# Interlock.net
KiCad netlist of a schematic drawn in EAGLE
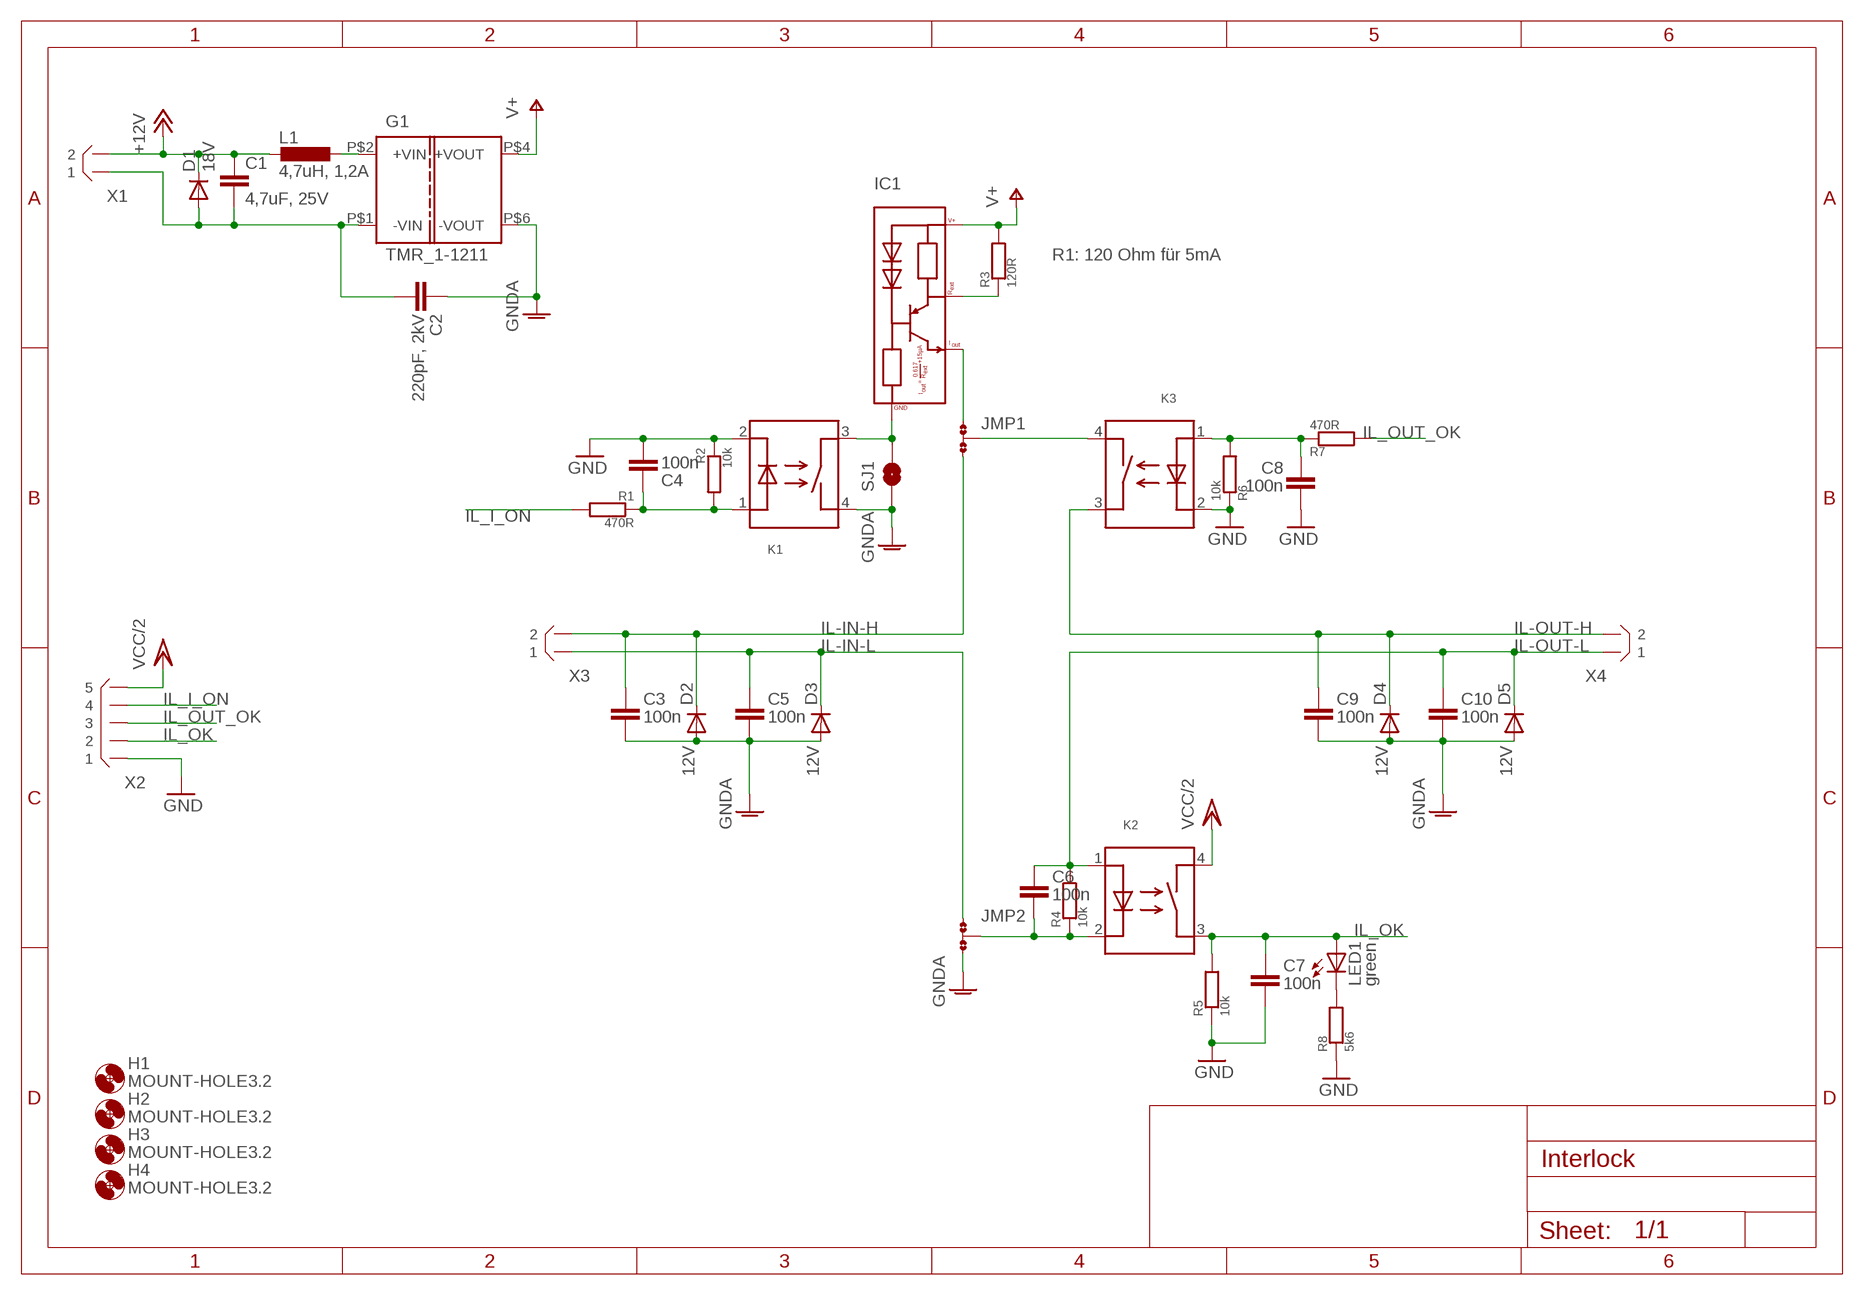
[diagram p0: schematic, sheet 1]

(export (version "E")
  (design (tool "Eeschema 10.0.6"))
  (components
    (comp (ref "C1")
      (value "4,7uF, 25V")
      (footprint "eagle-import:C0805")
      (libsource (lib "eagle-import") (part "C-EUC0805"))
    )
    (comp (ref "C2")
      (value "220pF, 2kV")
      (footprint "eagle-import:C1210_HV")
      (libsource (lib "eagle-import") (part "CC1210_HV"))
    )
    (comp (ref "C3")
      (value "100n")
      (footprint "eagle-import:C0805")
      (libsource (lib "eagle-import") (part "CSTD"))
    )
    (comp (ref "C4")
      (value "100n")
      (footprint "eagle-import:C0805")
      (libsource (lib "eagle-import") (part "CSTD"))
    )
    (comp (ref "C5")
      (value "100n")
      (footprint "eagle-import:C0805")
      (libsource (lib "eagle-import") (part "CSTD"))
    )
    (comp (ref "C6")
      (value "100n")
      (footprint "eagle-import:C0805")
      (libsource (lib "eagle-import") (part "CSTD"))
    )
    (comp (ref "C7")
      (value "100n")
      (footprint "eagle-import:C0805")
      (libsource (lib "eagle-import") (part "CSTD"))
    )
    (comp (ref "C8")
      (value "100n")
      (footprint "eagle-import:C0805")
      (libsource (lib "eagle-import") (part "CSTD"))
    )
    (comp (ref "C9")
      (value "100n")
      (footprint "eagle-import:C0805")
      (libsource (lib "eagle-import") (part "CSTD"))
    )
    (comp (ref "C10")
      (value "100n")
      (footprint "eagle-import:C0805")
      (libsource (lib "eagle-import") (part "CSTD"))
    )
    (comp (ref "D1")
      (value "18V")
      (footprint "eagle-import:DO214AA")
      (libsource (lib "eagle-import") (part "DIODE-DO214AA"))
    )
    (comp (ref "D2")
      (value "12V")
      (footprint "eagle-import:DO214AA")
      (libsource (lib "eagle-import") (part "DIODE-DO214AA"))
    )
    (comp (ref "D3")
      (value "12V")
      (footprint "eagle-import:DO214AA")
      (libsource (lib "eagle-import") (part "DIODE-DO214AA"))
    )
    (comp (ref "D4")
      (value "12V")
      (footprint "eagle-import:DO214AA")
      (libsource (lib "eagle-import") (part "DIODE-DO214AA"))
    )
    (comp (ref "D5")
      (value "12V")
      (footprint "eagle-import:DO214AA")
      (libsource (lib "eagle-import") (part "DIODE-DO214AA"))
    )
    (comp (ref "G1")
      (value "TMR_1-1211")
      (footprint "eagle-import:TMR_1-__1_")
      (libsource (lib "eagle-import") (part "TMR_1-??1?"))
    )
    (comp (ref "H1")
      (value "MOUNT-HOLE3.2")
      (footprint "eagle-import:3,2")
      (libsource (lib "eagle-import") (part "MOUNT-HOLE3.2"))
    )
    (comp (ref "H2")
      (value "MOUNT-HOLE3.2")
      (footprint "eagle-import:3,2")
      (libsource (lib "eagle-import") (part "MOUNT-HOLE3.2"))
    )
    (comp (ref "H3")
      (value "MOUNT-HOLE3.2")
      (footprint "eagle-import:3,2")
      (libsource (lib "eagle-import") (part "MOUNT-HOLE3.2"))
    )
    (comp (ref "H4")
      (value "MOUNT-HOLE3.2")
      (footprint "eagle-import:3,2")
      (libsource (lib "eagle-import") (part "MOUNT-HOLE3.2"))
    )
    (comp (ref "IC1")
      (value "PSSI2021SAY")
      (footprint "eagle-import:SOT353")
      (libsource (lib "eagle-import") (part "PSSI2021SAY"))
    )
    (comp (ref "JMP1")
      (value "0R-JUMPA")
      (footprint "eagle-import:A0R-JMP")
      (libsource (lib "eagle-import") (part "0R-JUMPA"))
    )
    (comp (ref "JMP2")
      (value "0R-JUMPA")
      (footprint "eagle-import:A0R-JMP")
      (libsource (lib "eagle-import") (part "0R-JUMPA"))
    )
    (comp (ref "K1")
      (value "ASSR-1218")
      (footprint "eagle-import:SO-4")
      (libsource (lib "eagle-import") (part "ASSR-1218"))
    )
    (comp (ref "K2")
      (value "ASSR-1218")
      (footprint "eagle-import:SO-4")
      (libsource (lib "eagle-import") (part "ASSR-1218"))
    )
    (comp (ref "K3")
      (value "ASSR-1218")
      (footprint "eagle-import:SO-4")
      (libsource (lib "eagle-import") (part "ASSR-1218"))
    )
    (comp (ref "L1")
      (value "4,7uH, 1,2A")
      (footprint "eagle-import:L3225M")
      (libsource (lib "eagle-import") (part "L-EUL3225M"))
    )
    (comp (ref "LED1")
      (value "green")
      (footprint "eagle-import:CHIPLED_0805")
      (libsource (lib "eagle-import") (part "LEDCHIPLED_0805"))
    )
    (comp (ref "R1")
      (value "470R")
      (footprint "eagle-import:R0805")
      (libsource (lib "eagle-import") (part "R"))
    )
    (comp (ref "R2")
      (value "10k")
      (footprint "eagle-import:R0805")
      (libsource (lib "eagle-import") (part "R"))
    )
    (comp (ref "R3")
      (value "120R")
      (footprint "eagle-import:R0805")
      (libsource (lib "eagle-import") (part "R"))
    )
    (comp (ref "R4")
      (value "10k")
      (footprint "eagle-import:R0805")
      (libsource (lib "eagle-import") (part "R"))
    )
    (comp (ref "R5")
      (value "10k")
      (footprint "eagle-import:R0805")
      (libsource (lib "eagle-import") (part "R"))
    )
    (comp (ref "R6")
      (value "10k")
      (footprint "eagle-import:R0805")
      (libsource (lib "eagle-import") (part "R"))
    )
    (comp (ref "R7")
      (value "470R")
      (footprint "eagle-import:R0805")
      (libsource (lib "eagle-import") (part "R"))
    )
    (comp (ref "R8")
      (value "5k6")
      (footprint "eagle-import:R0805")
      (libsource (lib "eagle-import") (part "R"))
    )
    (comp (ref "SJ1")
      (value "SOLDERJUMPERNO")
      (footprint "eagle-import:SJ_2S-NO")
      (libsource (lib "eagle-import") (part "SOLDERJUMPERNO"))
    )
    (comp (ref "X1")
      (value "B2B-XH")
      (footprint "eagle-import:B2B-XH")
      (libsource (lib "eagle-import") (part "?2B-XHB"))
    )
    (comp (ref "X2")
      (value "B5B-XH")
      (footprint "eagle-import:B5B-XH")
      (libsource (lib "eagle-import") (part "?5B-XHB"))
    )
    (comp (ref "X3")
      (value "B2B-XH")
      (footprint "eagle-import:B2B-XH")
      (libsource (lib "eagle-import") (part "?2B-XHB"))
    )
    (comp (ref "X4")
      (value "B2B-XH")
      (footprint "eagle-import:B2B-XH")
      (libsource (lib "eagle-import") (part "?2B-XHB"))
    )
  )
  (nets
    (net (code "1") (name "+12V") (class "Default")
      (node (ref "C1") (pin "1") (pinfunction "1_1") (pintype "passive"))
      (node (ref "D1") (pin "C") (pinfunction "C_C") (pintype "passive"))
      (node (ref "L1") (pin "2") (pinfunction "2_2") (pintype "passive"))
      (node (ref "X1") (pin "P$2") (pinfunction "2_P$2") (pintype "bidirectional"))
    )
    (net (code "2") (name "/IL-IN-H") (class "Default")
      (node (ref "C3") (pin "2") (pinfunction "2_2") (pintype "passive"))
      (node (ref "D2") (pin "C") (pinfunction "C_C") (pintype "passive"))
      (node (ref "JMP1") (pin "3") (pinfunction "3_3") (pintype "passive"))
      (node (ref "X3") (pin "P$2") (pinfunction "2_P$2") (pintype "bidirectional"))
    )
    (net (code "3") (name "/IL-IN-L") (class "Default")
      (node (ref "C5") (pin "2") (pinfunction "2_2") (pintype "passive"))
      (node (ref "D3") (pin "C") (pinfunction "C_C") (pintype "passive"))
      (node (ref "JMP2") (pin "3") (pinfunction "3_3") (pintype "passive"))
      (node (ref "X3") (pin "P$1") (pinfunction "1_P$1") (pintype "bidirectional"))
    )
    (net (code "4") (name "/IL-OUT-H") (class "Default")
      (node (ref "C9") (pin "2") (pinfunction "2_2") (pintype "passive"))
      (node (ref "D4") (pin "C") (pinfunction "C_C") (pintype "passive"))
      (node (ref "K3") (pin "3") (pinfunction "O2_3") (pintype "bidirectional"))
      (node (ref "X4") (pin "P$2") (pinfunction "2_P$2") (pintype "bidirectional"))
    )
    (net (code "5") (name "/IL-OUT-L") (class "Default")
      (node (ref "C10") (pin "2") (pinfunction "2_2") (pintype "passive"))
      (node (ref "C6") (pin "2") (pinfunction "2_2") (pintype "passive"))
      (node (ref "D5") (pin "C") (pinfunction "C_C") (pintype "passive"))
      (node (ref "K2") (pin "1") (pinfunction "I+_1") (pintype "bidirectional"))
      (node (ref "R4") (pin "2") (pinfunction "2_2") (pintype "passive"))
      (node (ref "X4") (pin "P$1") (pinfunction "1_P$1") (pintype "bidirectional"))
    )
    (net (code "6") (name "/IL_I_ON") (class "Default")
      (node (ref "R1") (pin "2") (pinfunction "2_2") (pintype "passive"))
      (node (ref "X2") (pin "P$4") (pinfunction "4_P$4") (pintype "bidirectional"))
    )
    (net (code "7") (name "/IL_OK") (class "Default")
      (node (ref "C7") (pin "2") (pinfunction "2_2") (pintype "passive"))
      (node (ref "K2") (pin "3") (pinfunction "O2_3") (pintype "bidirectional"))
      (node (ref "LED1") (pin "A") (pinfunction "A_A") (pintype "passive"))
      (node (ref "R5") (pin "2") (pinfunction "2_2") (pintype "passive"))
      (node (ref "X2") (pin "P$2") (pinfunction "2_P$2") (pintype "bidirectional"))
    )
    (net (code "8") (name "/IL_OUT_OK") (class "Default")
      (node (ref "R7") (pin "2") (pinfunction "2_2") (pintype "passive"))
      (node (ref "X2") (pin "P$3") (pinfunction "3_P$3") (pintype "bidirectional"))
    )
    (net (code "9") (name "GND") (class "Default")
      (node (ref "C4") (pin "1") (pinfunction "1_1") (pintype "passive"))
      (node (ref "C7") (pin "1") (pinfunction "1_1") (pintype "passive"))
      (node (ref "C8") (pin "1") (pinfunction "1_1") (pintype "passive"))
      (node (ref "K1") (pin "2") (pinfunction "I-_2") (pintype "bidirectional"))
      (node (ref "K3") (pin "2") (pinfunction "I-_2") (pintype "bidirectional"))
      (node (ref "R2") (pin "1") (pinfunction "1_1") (pintype "passive"))
      (node (ref "R5") (pin "1") (pinfunction "1_1") (pintype "passive"))
      (node (ref "R6") (pin "1") (pinfunction "1_1") (pintype "passive"))
      (node (ref "R8") (pin "1") (pinfunction "1_1") (pintype "passive"))
      (node (ref "X2") (pin "P$1") (pinfunction "1_P$1") (pintype "bidirectional"))
    )
    (net (code "10") (name "GNDA") (class "Default")
      (node (ref "C10") (pin "1") (pinfunction "1_1") (pintype "passive"))
      (node (ref "C2") (pin "P$2") (pinfunction "2_P$2") (pintype "passive"))
      (node (ref "C3") (pin "1") (pinfunction "1_1") (pintype "passive"))
      (node (ref "C5") (pin "1") (pinfunction "1_1") (pintype "passive"))
      (node (ref "C9") (pin "1") (pinfunction "1_1") (pintype "passive"))
      (node (ref "D2") (pin "A") (pinfunction "A_A") (pintype "passive"))
      (node (ref "D3") (pin "A") (pinfunction "A_A") (pintype "passive"))
      (node (ref "D4") (pin "A") (pinfunction "A_A") (pintype "passive"))
      (node (ref "D5") (pin "A") (pinfunction "A_A") (pintype "passive"))
      (node (ref "G1") (pin "P$6") (pinfunction "-VOUT_P$6") (pintype "bidirectional"))
      (node (ref "JMP2") (pin "1") (pinfunction "1_1") (pintype "passive"))
      (node (ref "K1") (pin "4") (pinfunction "O1_4") (pintype "bidirectional"))
      (node (ref "SJ1") (pin "1") (pinfunction "1_1") (pintype "passive"))
    )
    (net (code "11") (name "Net-(C2-1)") (class "Default")
      (node (ref "C1") (pin "2") (pinfunction "2_2") (pintype "passive"))
      (node (ref "C2") (pin "P$1") (pinfunction "1_P$1") (pintype "passive"))
      (node (ref "D1") (pin "A") (pinfunction "A_A") (pintype "passive"))
      (node (ref "G1") (pin "P$1") (pinfunction "-VIN_P$1") (pintype "bidirectional"))
      (node (ref "X1") (pin "P$1") (pinfunction "1_P$1") (pintype "bidirectional"))
    )
    (net (code "12") (name "Net-(G1-+VIN)") (class "Default")
      (node (ref "G1") (pin "P$2") (pinfunction "+VIN_P$2") (pintype "bidirectional"))
      (node (ref "L1") (pin "1") (pinfunction "1_1") (pintype "passive"))
    )
    (net (code "13") (name "Net-(IC1-GND)") (class "Default")
      (node (ref "IC1") (pin "3") (pinfunction "GND_3") (pintype "bidirectional"))
      (node (ref "K1") (pin "3") (pinfunction "O2_3") (pintype "bidirectional"))
      (node (ref "SJ1") (pin "2") (pinfunction "2_2") (pintype "passive"))
    )
    (net (code "14") (name "Net-(IC1-IOUT)") (class "Default")
      (node (ref "IC1") (pin "2") (pinfunction "IOUT_2") (pintype "bidirectional"))
      (node (ref "JMP1") (pin "1") (pinfunction "1_1") (pintype "passive"))
    )
    (net (code "15") (name "Net-(IC1-REXT)") (class "Default")
      (node (ref "IC1") (pin "4") (pinfunction "REXT_4") (pintype "bidirectional"))
      (node (ref "R3") (pin "1") (pinfunction "1_1") (pintype "passive"))
    )
    (net (code "16") (name "Net-(K1-I+)") (class "Default")
      (node (ref "C4") (pin "2") (pinfunction "2_2") (pintype "passive"))
      (node (ref "K1") (pin "1") (pinfunction "I+_1") (pintype "bidirectional"))
      (node (ref "R1") (pin "1") (pinfunction "1_1") (pintype "passive"))
      (node (ref "R2") (pin "2") (pinfunction "2_2") (pintype "passive"))
    )
    (net (code "17") (name "Net-(K2-I-)") (class "Default")
      (node (ref "C6") (pin "1") (pinfunction "1_1") (pintype "passive"))
      (node (ref "JMP2") (pin "2") (pinfunction "2_2") (pintype "passive"))
      (node (ref "K2") (pin "2") (pinfunction "I-_2") (pintype "bidirectional"))
      (node (ref "R4") (pin "1") (pinfunction "1_1") (pintype "passive"))
    )
    (net (code "18") (name "Net-(K3-I+)") (class "Default")
      (node (ref "C8") (pin "2") (pinfunction "2_2") (pintype "passive"))
      (node (ref "K3") (pin "1") (pinfunction "I+_1") (pintype "bidirectional"))
      (node (ref "R6") (pin "2") (pinfunction "2_2") (pintype "passive"))
      (node (ref "R7") (pin "1") (pinfunction "1_1") (pintype "passive"))
    )
    (net (code "19") (name "Net-(K3-O1)") (class "Default")
      (node (ref "JMP1") (pin "2") (pinfunction "2_2") (pintype "passive"))
      (node (ref "K3") (pin "4") (pinfunction "O1_4") (pintype "bidirectional"))
    )
    (net (code "20") (name "Net-(LED1-PadC)") (class "Default")
      (node (ref "LED1") (pin "C") (pinfunction "C_C") (pintype "passive"))
      (node (ref "R8") (pin "2") (pinfunction "2_2") (pintype "passive"))
    )
    (net (code "21") (name "V+") (class "Default")
      (node (ref "G1") (pin "P$4") (pinfunction "+VOUT_P$4") (pintype "bidirectional"))
      (node (ref "IC1") (pin "5") (pinfunction "VSS_5") (pintype "bidirectional"))
      (node (ref "R3") (pin "2") (pinfunction "2_2") (pintype "passive"))
    )
    (net (code "22") (name "VCC{slash}2") (class "Default")
      (node (ref "K2") (pin "4") (pinfunction "O1_4") (pintype "bidirectional"))
      (node (ref "X2") (pin "P$5") (pinfunction "5_P$5") (pintype "bidirectional"))
    )
  )
)
